# bldc_driver_board_easyeda.net
KiCad netlist of a schematic drawn in EasyEDA Pro
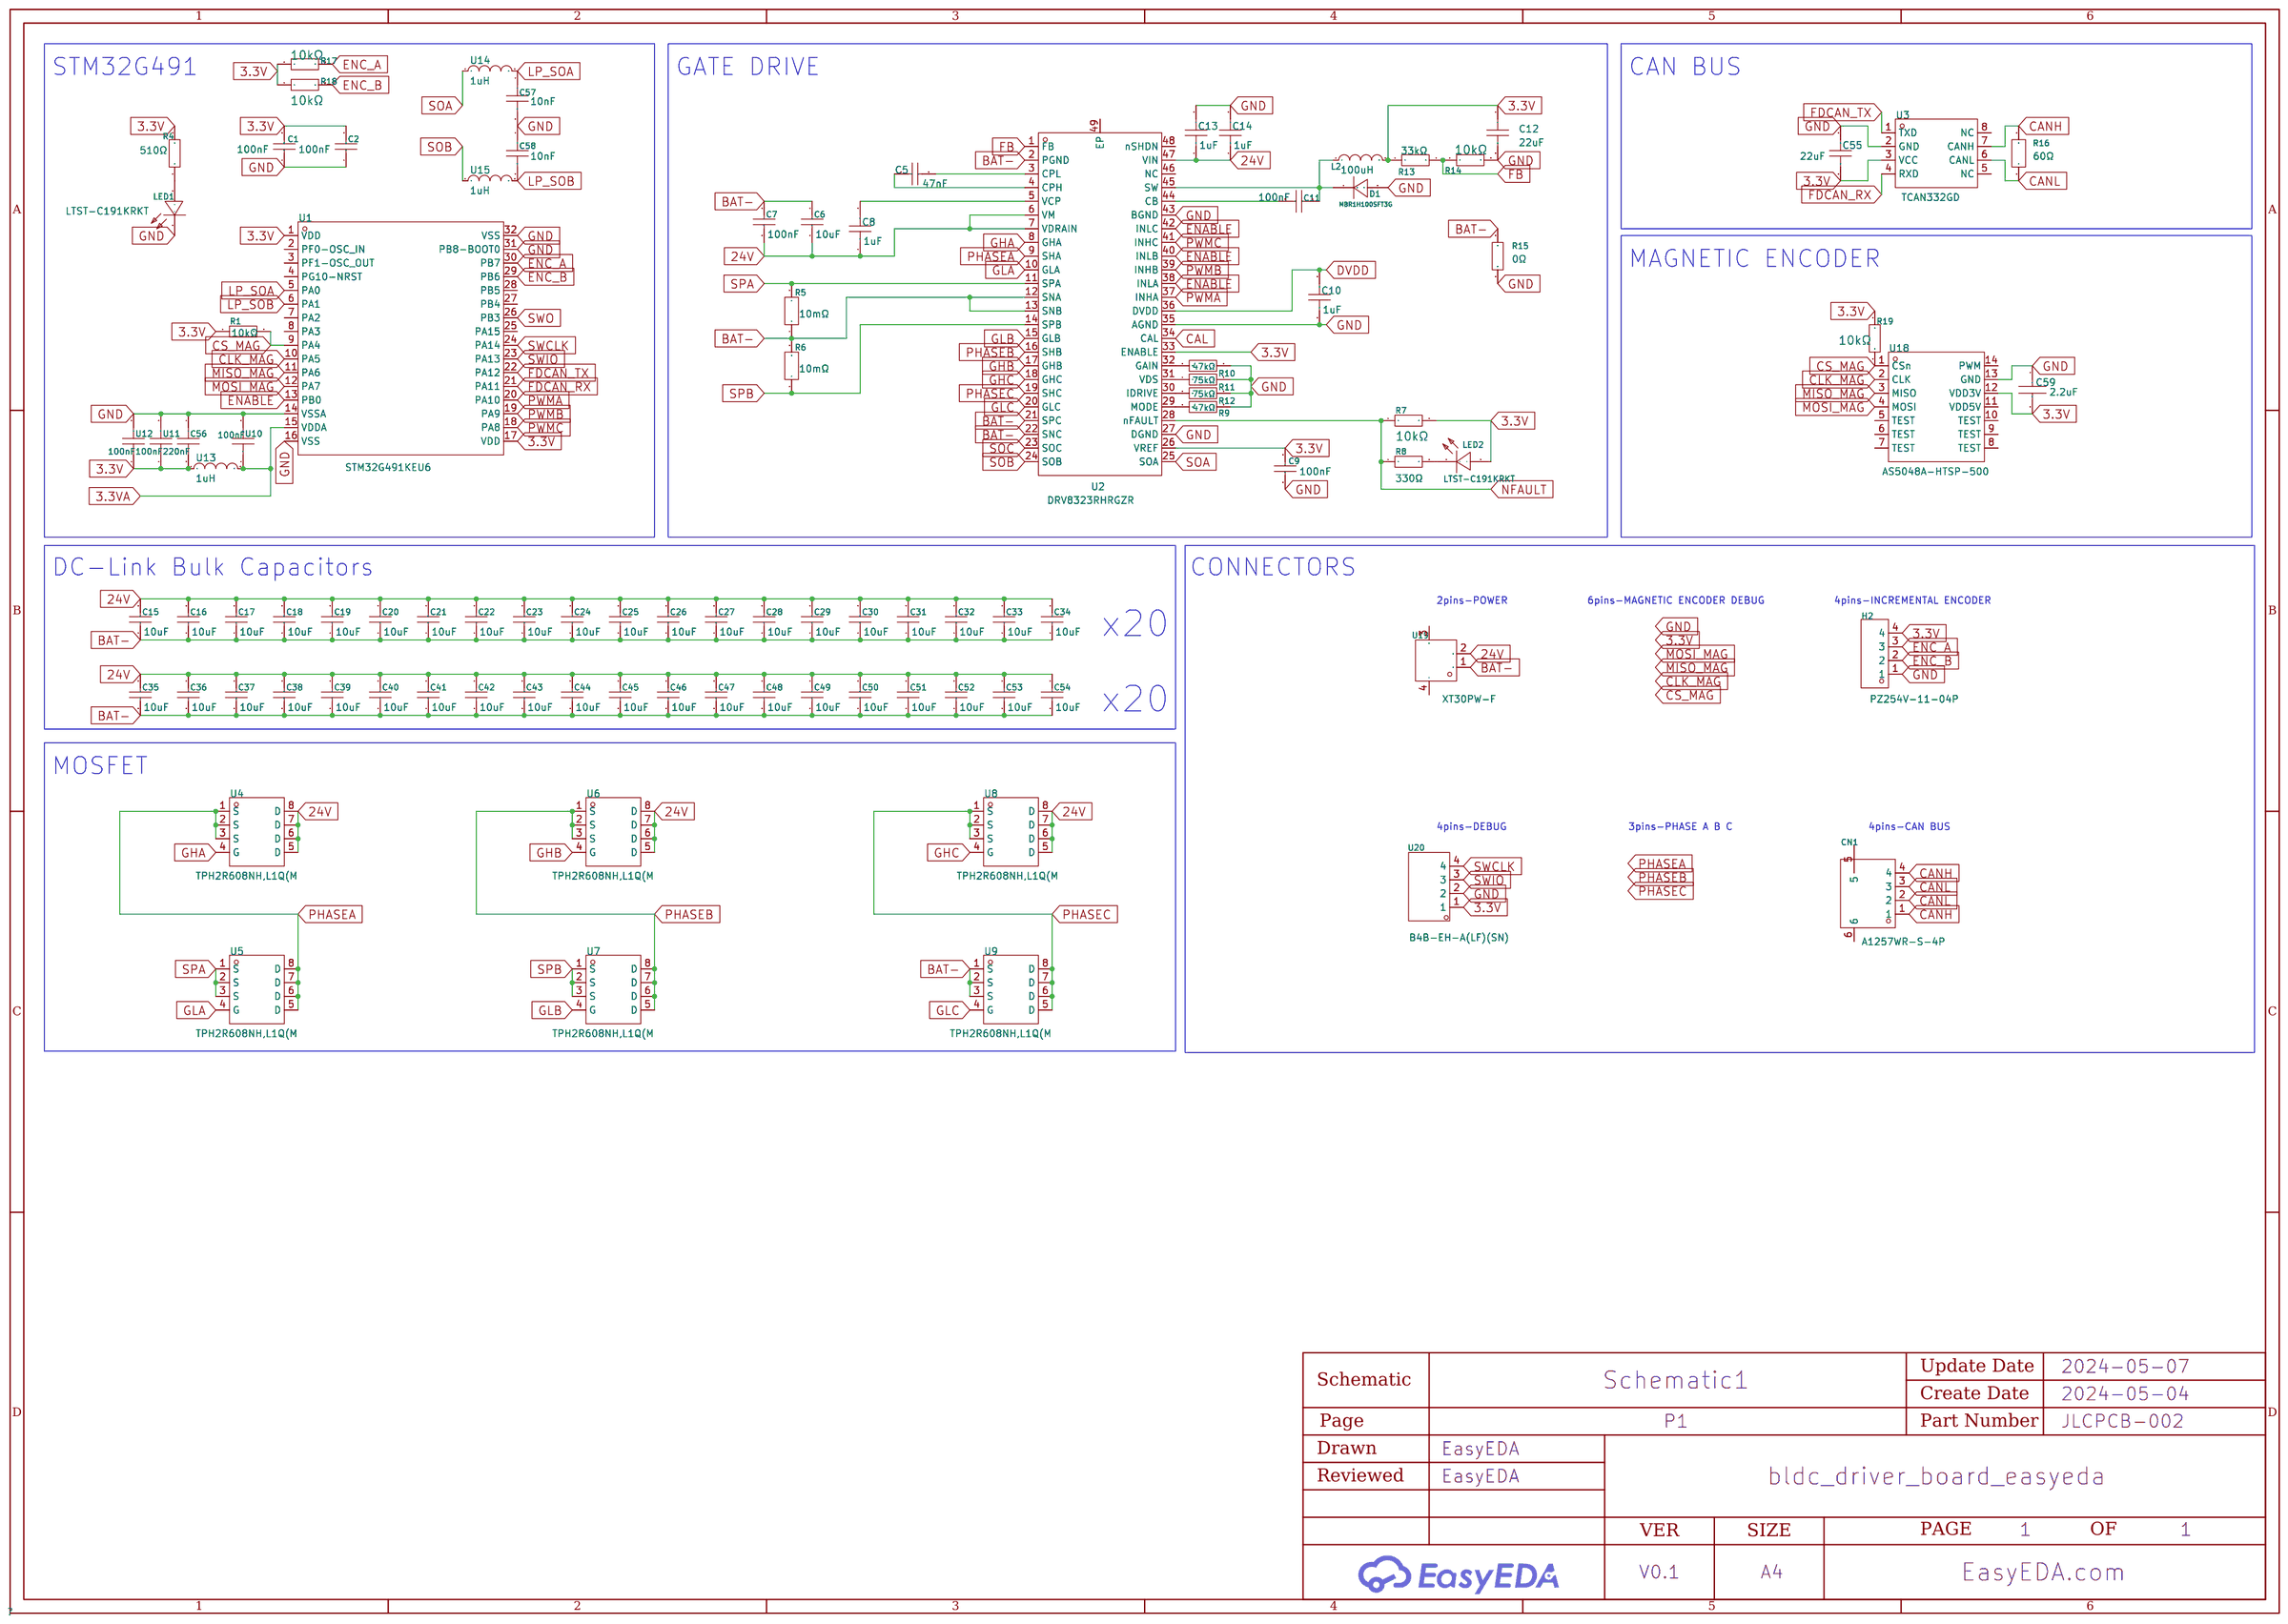
[diagram p0: schematic sheet]

(export (version "E")
  (design (tool "Eeschema 10.0.6"))
  (components
    (comp (ref "C1")
      (value "100nF")
      (footprint "easyedapro:C0603")
      (fields
        (field (name "Manufacturer Part") "CL10B104KO8NNNC")
        (field (name "Manufacturer") "SAMSUNG(三星)")
      )
      (libsource (lib "easyedapro") (part "CL10B104KO8NNNC"))
    )
    (comp (ref "C2")
      (value "100nF")
      (footprint "easyedapro:C0603")
      (fields
        (field (name "Manufacturer Part") "CL10B104KO8NNNC")
        (field (name "Manufacturer") "SAMSUNG(三星)")
      )
      (libsource (lib "easyedapro") (part "CL10B104KO8NNNC"))
    )
    (comp (ref "C5")
      (value "47nF")
      (footprint "easyedapro:C0805")
      (fields (field (name "Manufacturer Part") "0805B473K500NT") (field (name "Manufacturer") "FH(风华)"))
      (libsource (lib "easyedapro") (part "0805B473K500NT"))
    )
    (comp (ref "C6")
      (value "10uF")
      (footprint "easyedapro:C1206")
      (fields
        (field (name "Manufacturer Part") "CL31A106KBHNNNE")
        (field (name "Manufacturer") "SAMSUNG(三星)")
      )
      (libsource (lib "easyedapro") (part "CL31A106KBHNNNE"))
    )
    (comp (ref "C7")
      (value "100nF")
      (footprint "easyedapro:C1206")
      (fields (field (name "Manufacturer Part") "1206B104K500NT") (field (name "Manufacturer") "FH(风华)"))
      (libsource (lib "easyedapro") (part "1206B104K500NT"))
    )
    (comp (ref "C8")
      (value "1uF")
      (footprint "easyedapro:C0603")
      (fields
        (field (name "Manufacturer Part") "CL10A105KB8NNNC")
        (field (name "Manufacturer") "SAMSUNG(三星)")
      )
      (libsource (lib "easyedapro") (part "CL10A105KB8NNNC"))
    )
    (comp (ref "C9")
      (value "100nF")
      (footprint "easyedapro:C0603")
      (fields
        (field (name "Manufacturer Part") "CL10B104KO8NNNC")
        (field (name "Manufacturer") "SAMSUNG(三星)")
      )
      (libsource (lib "easyedapro") (part "CL10B104KO8NNNC"))
    )
    (comp (ref "C10")
      (value "1uF")
      (footprint "easyedapro:C0603")
      (fields
        (field (name "Manufacturer Part") "CL10A105KB8NNNC")
        (field (name "Manufacturer") "SAMSUNG(三星)")
      )
      (libsource (lib "easyedapro") (part "CL10A105KB8NNNC"))
    )
    (comp (ref "C11")
      (value "100nF")
      (footprint "easyedapro:C1206")
      (fields (field (name "Manufacturer Part") "1206B104K500NT") (field (name "Manufacturer") "FH(风华)"))
      (libsource (lib "easyedapro") (part "1206B104K500NT"))
    )
    (comp (ref "C12")
      (value "22uF")
      (footprint "easyedapro:C0603")
      (fields
        (field (name "Manufacturer Part") "CL10A226MQ8NRNE")
        (field (name "Manufacturer") "SAMSUNG(三星)")
      )
      (libsource (lib "easyedapro") (part "CL10A226MQ8NRNE"))
    )
    (comp (ref "C13")
      (value "1uF")
      (footprint "easyedapro:C0603")
      (fields
        (field (name "Manufacturer Part") "CL10A105KB8NNNC")
        (field (name "Manufacturer") "SAMSUNG(三星)")
      )
      (libsource (lib "easyedapro") (part "CL10A105KB8NNNC"))
    )
    (comp (ref "C14")
      (value "1uF")
      (footprint "easyedapro:C0603")
      (fields
        (field (name "Manufacturer Part") "CL10A105KB8NNNC")
        (field (name "Manufacturer") "SAMSUNG(三星)")
      )
      (libsource (lib "easyedapro") (part "CL10A105KB8NNNC"))
    )
    (comp (ref "C15")
      (value "10uF")
      (footprint "easyedapro:C1206")
      (fields
        (field (name "Manufacturer Part") "CL31A106KBHNNNE")
        (field (name "Manufacturer") "SAMSUNG(三星)")
      )
      (libsource (lib "easyedapro") (part "CL31A106KBHNNNE"))
    )
    (comp (ref "C16")
      (value "10uF")
      (footprint "easyedapro:C1206")
      (fields
        (field (name "Manufacturer Part") "CL31A106KBHNNNE")
        (field (name "Manufacturer") "SAMSUNG(三星)")
      )
      (libsource (lib "easyedapro") (part "CL31A106KBHNNNE"))
    )
    (comp (ref "C17")
      (value "10uF")
      (footprint "easyedapro:C1206")
      (fields
        (field (name "Manufacturer Part") "CL31A106KBHNNNE")
        (field (name "Manufacturer") "SAMSUNG(三星)")
      )
      (libsource (lib "easyedapro") (part "CL31A106KBHNNNE"))
    )
    (comp (ref "C18")
      (value "10uF")
      (footprint "easyedapro:C1206")
      (fields
        (field (name "Manufacturer Part") "CL31A106KBHNNNE")
        (field (name "Manufacturer") "SAMSUNG(三星)")
      )
      (libsource (lib "easyedapro") (part "CL31A106KBHNNNE"))
    )
    (comp (ref "C19")
      (value "10uF")
      (footprint "easyedapro:C1206")
      (fields
        (field (name "Manufacturer Part") "CL31A106KBHNNNE")
        (field (name "Manufacturer") "SAMSUNG(三星)")
      )
      (libsource (lib "easyedapro") (part "CL31A106KBHNNNE"))
    )
    (comp (ref "C20")
      (value "10uF")
      (footprint "easyedapro:C1206")
      (fields
        (field (name "Manufacturer Part") "CL31A106KBHNNNE")
        (field (name "Manufacturer") "SAMSUNG(三星)")
      )
      (libsource (lib "easyedapro") (part "CL31A106KBHNNNE"))
    )
    (comp (ref "C21")
      (value "10uF")
      (footprint "easyedapro:C1206")
      (fields
        (field (name "Manufacturer Part") "CL31A106KBHNNNE")
        (field (name "Manufacturer") "SAMSUNG(三星)")
      )
      (libsource (lib "easyedapro") (part "CL31A106KBHNNNE"))
    )
    (comp (ref "C22")
      (value "10uF")
      (footprint "easyedapro:C1206")
      (fields
        (field (name "Manufacturer Part") "CL31A106KBHNNNE")
        (field (name "Manufacturer") "SAMSUNG(三星)")
      )
      (libsource (lib "easyedapro") (part "CL31A106KBHNNNE"))
    )
    (comp (ref "C23")
      (value "10uF")
      (footprint "easyedapro:C1206")
      (fields
        (field (name "Manufacturer Part") "CL31A106KBHNNNE")
        (field (name "Manufacturer") "SAMSUNG(三星)")
      )
      (libsource (lib "easyedapro") (part "CL31A106KBHNNNE"))
    )
    (comp (ref "C24")
      (value "10uF")
      (footprint "easyedapro:C1206")
      (fields
        (field (name "Manufacturer Part") "CL31A106KBHNNNE")
        (field (name "Manufacturer") "SAMSUNG(三星)")
      )
      (libsource (lib "easyedapro") (part "CL31A106KBHNNNE"))
    )
    (comp (ref "C25")
      (value "10uF")
      (footprint "easyedapro:C1206")
      (fields
        (field (name "Manufacturer Part") "CL31A106KBHNNNE")
        (field (name "Manufacturer") "SAMSUNG(三星)")
      )
      (libsource (lib "easyedapro") (part "CL31A106KBHNNNE"))
    )
    (comp (ref "C26")
      (value "10uF")
      (footprint "easyedapro:C1206")
      (fields
        (field (name "Manufacturer Part") "CL31A106KBHNNNE")
        (field (name "Manufacturer") "SAMSUNG(三星)")
      )
      (libsource (lib "easyedapro") (part "CL31A106KBHNNNE"))
    )
    (comp (ref "C27")
      (value "10uF")
      (footprint "easyedapro:C1206")
      (fields
        (field (name "Manufacturer Part") "CL31A106KBHNNNE")
        (field (name "Manufacturer") "SAMSUNG(三星)")
      )
      (libsource (lib "easyedapro") (part "CL31A106KBHNNNE"))
    )
    (comp (ref "C28")
      (value "10uF")
      (footprint "easyedapro:C1206")
      (fields
        (field (name "Manufacturer Part") "CL31A106KBHNNNE")
        (field (name "Manufacturer") "SAMSUNG(三星)")
      )
      (libsource (lib "easyedapro") (part "CL31A106KBHNNNE"))
    )
    (comp (ref "C29")
      (value "10uF")
      (footprint "easyedapro:C1206")
      (fields
        (field (name "Manufacturer Part") "CL31A106KBHNNNE")
        (field (name "Manufacturer") "SAMSUNG(三星)")
      )
      (libsource (lib "easyedapro") (part "CL31A106KBHNNNE"))
    )
    (comp (ref "C30")
      (value "10uF")
      (footprint "easyedapro:C1206")
      (fields
        (field (name "Manufacturer Part") "CL31A106KBHNNNE")
        (field (name "Manufacturer") "SAMSUNG(三星)")
      )
      (libsource (lib "easyedapro") (part "CL31A106KBHNNNE"))
    )
    (comp (ref "C31")
      (value "10uF")
      (footprint "easyedapro:C1206")
      (fields
        (field (name "Manufacturer Part") "CL31A106KBHNNNE")
        (field (name "Manufacturer") "SAMSUNG(三星)")
      )
      (libsource (lib "easyedapro") (part "CL31A106KBHNNNE"))
    )
    (comp (ref "C32")
      (value "10uF")
      (footprint "easyedapro:C1206")
      (fields
        (field (name "Manufacturer Part") "CL31A106KBHNNNE")
        (field (name "Manufacturer") "SAMSUNG(三星)")
      )
      (libsource (lib "easyedapro") (part "CL31A106KBHNNNE"))
    )
    (comp (ref "C33")
      (value "10uF")
      (footprint "easyedapro:C1206")
      (fields
        (field (name "Manufacturer Part") "CL31A106KBHNNNE")
        (field (name "Manufacturer") "SAMSUNG(三星)")
      )
      (libsource (lib "easyedapro") (part "CL31A106KBHNNNE"))
    )
    (comp (ref "C34")
      (value "10uF")
      (footprint "easyedapro:C1206")
      (fields
        (field (name "Manufacturer Part") "CL31A106KBHNNNE")
        (field (name "Manufacturer") "SAMSUNG(三星)")
      )
      (libsource (lib "easyedapro") (part "CL31A106KBHNNNE"))
    )
    (comp (ref "C35")
      (value "10uF")
      (footprint "easyedapro:C1206")
      (fields
        (field (name "Manufacturer Part") "CL31A106KBHNNNE")
        (field (name "Manufacturer") "SAMSUNG(三星)")
      )
      (libsource (lib "easyedapro") (part "CL31A106KBHNNNE"))
    )
    (comp (ref "C36")
      (value "10uF")
      (footprint "easyedapro:C1206")
      (fields
        (field (name "Manufacturer Part") "CL31A106KBHNNNE")
        (field (name "Manufacturer") "SAMSUNG(三星)")
      )
      (libsource (lib "easyedapro") (part "CL31A106KBHNNNE"))
    )
    (comp (ref "C37")
      (value "10uF")
      (footprint "easyedapro:C1206")
      (fields
        (field (name "Manufacturer Part") "CL31A106KBHNNNE")
        (field (name "Manufacturer") "SAMSUNG(三星)")
      )
      (libsource (lib "easyedapro") (part "CL31A106KBHNNNE"))
    )
    (comp (ref "C38")
      (value "10uF")
      (footprint "easyedapro:C1206")
      (fields
        (field (name "Manufacturer Part") "CL31A106KBHNNNE")
        (field (name "Manufacturer") "SAMSUNG(三星)")
      )
      (libsource (lib "easyedapro") (part "CL31A106KBHNNNE"))
    )
    (comp (ref "C39")
      (value "10uF")
      (footprint "easyedapro:C1206")
      (fields
        (field (name "Manufacturer Part") "CL31A106KBHNNNE")
        (field (name "Manufacturer") "SAMSUNG(三星)")
      )
      (libsource (lib "easyedapro") (part "CL31A106KBHNNNE"))
    )
    (comp (ref "C40")
      (value "10uF")
      (footprint "easyedapro:C1206")
      (fields
        (field (name "Manufacturer Part") "CL31A106KBHNNNE")
        (field (name "Manufacturer") "SAMSUNG(三星)")
      )
      (libsource (lib "easyedapro") (part "CL31A106KBHNNNE"))
    )
    (comp (ref "C41")
      (value "10uF")
      (footprint "easyedapro:C1206")
      (fields
        (field (name "Manufacturer Part") "CL31A106KBHNNNE")
        (field (name "Manufacturer") "SAMSUNG(三星)")
      )
      (libsource (lib "easyedapro") (part "CL31A106KBHNNNE"))
    )
    (comp (ref "C42")
      (value "10uF")
      (footprint "easyedapro:C1206")
      (fields
        (field (name "Manufacturer Part") "CL31A106KBHNNNE")
        (field (name "Manufacturer") "SAMSUNG(三星)")
      )
      (libsource (lib "easyedapro") (part "CL31A106KBHNNNE"))
    )
    (comp (ref "C43")
      (value "10uF")
      (footprint "easyedapro:C1206")
      (fields
        (field (name "Manufacturer Part") "CL31A106KBHNNNE")
        (field (name "Manufacturer") "SAMSUNG(三星)")
      )
      (libsource (lib "easyedapro") (part "CL31A106KBHNNNE"))
    )
    (comp (ref "C44")
      (value "10uF")
      (footprint "easyedapro:C1206")
      (fields
        (field (name "Manufacturer Part") "CL31A106KBHNNNE")
        (field (name "Manufacturer") "SAMSUNG(三星)")
      )
      (libsource (lib "easyedapro") (part "CL31A106KBHNNNE"))
    )
    (comp (ref "C45")
      (value "10uF")
      (footprint "easyedapro:C1206")
      (fields
        (field (name "Manufacturer Part") "CL31A106KBHNNNE")
        (field (name "Manufacturer") "SAMSUNG(三星)")
      )
      (libsource (lib "easyedapro") (part "CL31A106KBHNNNE"))
    )
    (comp (ref "C46")
      (value "10uF")
      (footprint "easyedapro:C1206")
      (fields
        (field (name "Manufacturer Part") "CL31A106KBHNNNE")
        (field (name "Manufacturer") "SAMSUNG(三星)")
      )
      (libsource (lib "easyedapro") (part "CL31A106KBHNNNE"))
    )
    (comp (ref "C47")
      (value "10uF")
      (footprint "easyedapro:C1206")
      (fields
        (field (name "Manufacturer Part") "CL31A106KBHNNNE")
        (field (name "Manufacturer") "SAMSUNG(三星)")
      )
      (libsource (lib "easyedapro") (part "CL31A106KBHNNNE"))
    )
    (comp (ref "C48")
      (value "10uF")
      (footprint "easyedapro:C1206")
      (fields
        (field (name "Manufacturer Part") "CL31A106KBHNNNE")
        (field (name "Manufacturer") "SAMSUNG(三星)")
      )
      (libsource (lib "easyedapro") (part "CL31A106KBHNNNE"))
    )
    (comp (ref "C49")
      (value "10uF")
      (footprint "easyedapro:C1206")
      (fields
        (field (name "Manufacturer Part") "CL31A106KBHNNNE")
        (field (name "Manufacturer") "SAMSUNG(三星)")
      )
      (libsource (lib "easyedapro") (part "CL31A106KBHNNNE"))
    )
    (comp (ref "C50")
      (value "10uF")
      (footprint "easyedapro:C1206")
      (fields
        (field (name "Manufacturer Part") "CL31A106KBHNNNE")
        (field (name "Manufacturer") "SAMSUNG(三星)")
      )
      (libsource (lib "easyedapro") (part "CL31A106KBHNNNE"))
    )
    (comp (ref "C51")
      (value "10uF")
      (footprint "easyedapro:C1206")
      (fields
        (field (name "Manufacturer Part") "CL31A106KBHNNNE")
        (field (name "Manufacturer") "SAMSUNG(三星)")
      )
      (libsource (lib "easyedapro") (part "CL31A106KBHNNNE"))
    )
    (comp (ref "C52")
      (value "10uF")
      (footprint "easyedapro:C1206")
      (fields
        (field (name "Manufacturer Part") "CL31A106KBHNNNE")
        (field (name "Manufacturer") "SAMSUNG(三星)")
      )
      (libsource (lib "easyedapro") (part "CL31A106KBHNNNE"))
    )
    (comp (ref "C53")
      (value "10uF")
      (footprint "easyedapro:C1206")
      (fields
        (field (name "Manufacturer Part") "CL31A106KBHNNNE")
        (field (name "Manufacturer") "SAMSUNG(三星)")
      )
      (libsource (lib "easyedapro") (part "CL31A106KBHNNNE"))
    )
    (comp (ref "C54")
      (value "10uF")
      (footprint "easyedapro:C1206")
      (fields
        (field (name "Manufacturer Part") "CL31A106KBHNNNE")
        (field (name "Manufacturer") "SAMSUNG(三星)")
      )
      (libsource (lib "easyedapro") (part "CL31A106KBHNNNE"))
    )
    (comp (ref "C55")
      (value "22uF")
      (footprint "easyedapro:C0603")
      (fields
        (field (name "Manufacturer Part") "CL10A226MQ8NRNE")
        (field (name "Manufacturer") "SAMSUNG(三星)")
      )
      (libsource (lib "easyedapro") (part "CL10A226MQ8NRNE"))
    )
    (comp (ref "C56")
      (value "220nF")
      (footprint "easyedapro:C0201")
      (fields (field (name "Manufacturer Part") "C0603X5R0J224KT00NN") (field (name "Manufacturer") "TDK"))
      (libsource (lib "easyedapro") (part "C0603X5R0J224KT00NN"))
    )
    (comp (ref "C57")
      (value "10nF")
      (footprint "easyedapro:C01005")
      (fields
        (field (name "Manufacturer Part") "CC0100KRX5R5BB103")
        (field (name "Manufacturer") "YAGEO(国巨)")
      )
      (libsource (lib "easyedapro") (part "CC0100KRX5R5BB103"))
    )
    (comp (ref "C58")
      (value "10nF")
      (footprint "easyedapro:C01005")
      (fields
        (field (name "Manufacturer Part") "CC0100KRX5R5BB103")
        (field (name "Manufacturer") "YAGEO(国巨)")
      )
      (libsource (lib "easyedapro") (part "CC0100KRX5R5BB103"))
    )
    (comp (ref "C59")
      (value "2.2uF")
      (footprint "easyedapro:C0402")
      (fields
        (field (name "Manufacturer Part") "CL05A225MQ5NSNC")
        (field (name "Manufacturer") "SAMSUNG(三星)")
      )
      (libsource (lib "easyedapro") (part "CL05A225MQ5NSNC"))
    )
    (comp (ref "CN1")
      (value "A1257WR-S-4P")
      (footprint "easyedapro:CONN-SMD_A1257WR-S-4P")
      (fields (field (name "Manufacturer") "CJT(长江连接器)"))
      (libsource (lib "easyedapro") (part "A1257WR-S-4P"))
    )
    (comp (ref "D1")
      (value "MBR1H100SFT3G")
      (footprint "easyedapro:SOD-123F_L2.8-W1.8-LS3.7-RD")
      (fields (field (name "Manufacturer") "onsemi(安森美)"))
      (libsource (lib "easyedapro") (part "MBR1H100SFT3G"))
    )
    (comp (ref "H2")
      (value "PZ254V-11-04P")
      (footprint "easyedapro:HDR-TH_4P-P2.54-V-M")
      (fields (field (name "Manufacturer") "XFCN(兴飞)"))
      (libsource (lib "easyedapro") (part "PZ254V-11-04P"))
    )
    (comp (ref "L2")
      (value "100uH")
      (footprint "easyedapro:IND-SMD_L4.0-W4.0")
      (fields
        (field (name "Manufacturer Part") "ASPIAIG-S4035-101M-T")
        (field (name "Manufacturer") "ABRACON")
      )
      (libsource (lib "easyedapro") (part "ASPIAIG-S4035-101M-T"))
    )
    (comp (ref "LED1")
      (value "LTST-C191KRKT")
      (footprint "easyedapro:LED0603-RD")
      (fields (field (name "Manufacturer") "LITEON(光宝)"))
      (libsource (lib "easyedapro") (part "LTST-C191KRKT"))
    )
    (comp (ref "LED2")
      (value "LTST-C191KRKT")
      (footprint "easyedapro:LED0603-RD")
      (fields (field (name "Manufacturer") "LITEON(光宝)"))
      (libsource (lib "easyedapro") (part "LTST-C191KRKT"))
    )
    (comp (ref "R1")
      (value "10kΩ")
      (footprint "easyedapro:R0603")
      (fields
        (field (name "Manufacturer Part") "0603WAF1002T5E")
        (field (name "Manufacturer") "UNI-ROYAL(厚声)")
      )
      (libsource (lib "easyedapro") (part "0603WAF1002T5E"))
    )
    (comp (ref "R4")
      (value "510Ω")
      (footprint "easyedapro:R0603")
      (fields
        (field (name "Manufacturer Part") "0603WAF5100T5E")
        (field (name "Manufacturer") "UNI-ROYAL(厚声)")
      )
      (libsource (lib "easyedapro") (part "0603WAF5100T5E"))
    )
    (comp (ref "R5")
      (value "10mΩ")
      (footprint "easyedapro:RES-SMD_L6.4-W3.2-R2512")
      (fields
        (field (name "Manufacturer Part") "HoJLR2512-3W-10mR-1%")
        (field (name "Manufacturer") "Milliohm(毫欧)")
      )
      (libsource (lib "easyedapro") (part "HOJLR2512-3W-10MR-1%"))
    )
    (comp (ref "R6")
      (value "10mΩ")
      (footprint "easyedapro:RES-SMD_L6.4-W3.2-R2512")
      (fields
        (field (name "Manufacturer Part") "HoJLR2512-3W-10mR-1%")
        (field (name "Manufacturer") "Milliohm(毫欧)")
      )
      (libsource (lib "easyedapro") (part "HOJLR2512-3W-10MR-1%"))
    )
    (comp (ref "R7")
      (value "10kΩ")
      (footprint "easyedapro:R0603")
      (fields
        (field (name "Manufacturer Part") "0603WAF1002T5E")
        (field (name "Manufacturer") "UNI-ROYAL(厚声)")
      )
      (libsource (lib "easyedapro") (part "0603WAF1002T5E"))
    )
    (comp (ref "R8")
      (value "330Ω")
      (footprint "easyedapro:R0603")
      (fields
        (field (name "Manufacturer Part") "0603WAF3300T5E")
        (field (name "Manufacturer") "UNI-ROYAL(厚声)")
      )
      (libsource (lib "easyedapro") (part "0603WAF3300T5E"))
    )
    (comp (ref "R9")
      (value "47kΩ")
      (footprint "easyedapro:R0603")
      (fields
        (field (name "Manufacturer Part") "0603WAF4702T5E")
        (field (name "Manufacturer") "UNI-ROYAL(厚声)")
      )
      (libsource (lib "easyedapro") (part "0603WAF4702T5E"))
    )
    (comp (ref "R10")
      (value "47kΩ")
      (footprint "easyedapro:R0603")
      (fields
        (field (name "Manufacturer Part") "0603WAF4702T5E")
        (field (name "Manufacturer") "UNI-ROYAL(厚声)")
      )
      (libsource (lib "easyedapro") (part "0603WAF4702T5E"))
    )
    (comp (ref "R11")
      (value "75kΩ")
      (footprint "easyedapro:R0603")
      (fields
        (field (name "Manufacturer Part") "0603WAF7502T5E")
        (field (name "Manufacturer") "UNI-ROYAL(厚声)")
      )
      (libsource (lib "easyedapro") (part "0603WAF7502T5E"))
    )
    (comp (ref "R12")
      (value "75kΩ")
      (footprint "easyedapro:R0603")
      (fields
        (field (name "Manufacturer Part") "0603WAF7502T5E")
        (field (name "Manufacturer") "UNI-ROYAL(厚声)")
      )
      (libsource (lib "easyedapro") (part "0603WAF7502T5E"))
    )
    (comp (ref "R13")
      (value "33kΩ")
      (footprint "easyedapro:R0603")
      (fields
        (field (name "Manufacturer Part") "0603WAF3302T5E")
        (field (name "Manufacturer") "UNI-ROYAL(厚声)")
      )
      (libsource (lib "easyedapro") (part "0603WAF3302T5E"))
    )
    (comp (ref "R14")
      (value "10kΩ")
      (footprint "easyedapro:R0603")
      (fields
        (field (name "Manufacturer Part") "0603WAF1002T5E")
        (field (name "Manufacturer") "UNI-ROYAL(厚声)")
      )
      (libsource (lib "easyedapro") (part "0603WAF1002T5E"))
    )
    (comp (ref "R15")
      (value "0Ω")
      (footprint "easyedapro:R1206")
      (fields
        (field (name "Manufacturer Part") "1206W4F0000T5E")
        (field (name "Manufacturer") "UNI-ROYAL(厚声)")
      )
      (libsource (lib "easyedapro") (part "1206W4F0000T5E"))
    )
    (comp (ref "R16")
      (value "60Ω")
      (footprint "easyedapro:R0603")
      (fields (field (name "Manufacturer Part") "RTT0360R0FTP") (field (name "Manufacturer") "RALEC(旺诠)"))
      (libsource (lib "easyedapro") (part "RTT0360R0FTP"))
    )
    (comp (ref "R17")
      (value "10kΩ")
      (footprint "easyedapro:R0603")
      (fields
        (field (name "Manufacturer Part") "0603WAF1002T5E")
        (field (name "Manufacturer") "UNI-ROYAL(厚声)")
      )
      (libsource (lib "easyedapro") (part "0603WAF1002T5E"))
    )
    (comp (ref "R18")
      (value "10kΩ")
      (footprint "easyedapro:R0603")
      (fields
        (field (name "Manufacturer Part") "0603WAF1002T5E")
        (field (name "Manufacturer") "UNI-ROYAL(厚声)")
      )
      (libsource (lib "easyedapro") (part "0603WAF1002T5E"))
    )
    (comp (ref "R19")
      (value "10kΩ")
      (footprint "easyedapro:R0603")
      (fields
        (field (name "Manufacturer Part") "0603WAF1002T5E")
        (field (name "Manufacturer") "UNI-ROYAL(厚声)")
      )
      (libsource (lib "easyedapro") (part "0603WAF1002T5E"))
    )
    (comp (ref "U1")
      (value "STM32G491KEU6")
      (footprint "easyedapro:UFQFPN-32_L5.0-W5.0-P0.50-TL-1")
      (fields (field (name "Manufacturer") "ST(意法半导体)"))
      (libsource (lib "easyedapro") (part "STM32G491KEU6"))
    )
    (comp (ref "U2")
      (value "DRV8323RHRGZR")
      (footprint "easyedapro:VQFN-48_L7.0-W7.0-P0.50-TL-EP5.1")
      (fields (field (name "Manufacturer") "TI(德州仪器)"))
      (libsource (lib "easyedapro") (part "DRV8323RHRGZR"))
    )
    (comp (ref "U3")
      (value "TCAN332GD")
      (footprint "easyedapro:SOIC-8_L4.9-W3.9-P1.27-LS6.0-BL")
      (fields (field (name "Manufacturer") "TI(德州仪器)"))
      (libsource (lib "easyedapro") (part "TCAN332GD"))
    )
    (comp (ref "U4")
      (value "TPH2R608NH,L1Q(M")
      (footprint "easyedapro:POWERVDFN-8_L5.0-W5.0-P1.27-LS6.0-BL")
      (fields (field (name "Manufacturer") "TOSHIBA(东芝)"))
      (libsource (lib "easyedapro") (part "TPH2R608NH,L1Q(M"))
    )
    (comp (ref "U5")
      (value "TPH2R608NH,L1Q(M")
      (footprint "easyedapro:POWERVDFN-8_L5.0-W5.0-P1.27-LS6.0-BL")
      (fields (field (name "Manufacturer") "TOSHIBA(东芝)"))
      (libsource (lib "easyedapro") (part "TPH2R608NH,L1Q(M"))
    )
    (comp (ref "U6")
      (value "TPH2R608NH,L1Q(M")
      (footprint "easyedapro:POWERVDFN-8_L5.0-W5.0-P1.27-LS6.0-BL")
      (fields (field (name "Manufacturer") "TOSHIBA(东芝)"))
      (libsource (lib "easyedapro") (part "TPH2R608NH,L1Q(M"))
    )
    (comp (ref "U7")
      (value "TPH2R608NH,L1Q(M")
      (footprint "easyedapro:POWERVDFN-8_L5.0-W5.0-P1.27-LS6.0-BL")
      (fields (field (name "Manufacturer") "TOSHIBA(东芝)"))
      (libsource (lib "easyedapro") (part "TPH2R608NH,L1Q(M"))
    )
    (comp (ref "U8")
      (value "TPH2R608NH,L1Q(M")
      (footprint "easyedapro:POWERVDFN-8_L5.0-W5.0-P1.27-LS6.0-BL")
      (fields (field (name "Manufacturer") "TOSHIBA(东芝)"))
      (libsource (lib "easyedapro") (part "TPH2R608NH,L1Q(M"))
    )
    (comp (ref "U9")
      (value "TPH2R608NH,L1Q(M")
      (footprint "easyedapro:POWERVDFN-8_L5.0-W5.0-P1.27-LS6.0-BL")
      (fields (field (name "Manufacturer") "TOSHIBA(东芝)"))
      (libsource (lib "easyedapro") (part "TPH2R608NH,L1Q(M"))
    )
    (comp (ref "U10")
      (value "100nF")
      (footprint "easyedapro:C0603")
      (fields (field (name "Manufacturer Part") "06036D104KAT2A") (field (name "Manufacturer") "Kyocera AVX"))
      (libsource (lib "easyedapro") (part "06036D104KAT2A"))
    )
    (comp (ref "U11")
      (value "100nF")
      (footprint "easyedapro:C0603")
      (fields (field (name "Manufacturer Part") "06036D104KAT2A") (field (name "Manufacturer") "Kyocera AVX"))
      (libsource (lib "easyedapro") (part "06036D104KAT2A"))
    )
    (comp (ref "U12")
      (value "100nF")
      (footprint "easyedapro:C0603")
      (fields (field (name "Manufacturer Part") "06036D104KAT2A") (field (name "Manufacturer") "Kyocera AVX"))
      (libsource (lib "easyedapro") (part "06036D104KAT2A"))
    )
    (comp (ref "U13")
      (value "1uH")
      (footprint "easyedapro:L0603")
      (fields (field (name "Manufacturer Part") "YL160808-1R0K") (field (name "Manufacturer") "YJYCOIN(益嘉源)"))
      (libsource (lib "easyedapro") (part "YL160808-1R0K"))
    )
    (comp (ref "U14")
      (value "1uH")
      (footprint "easyedapro:L0603")
      (fields (field (name "Manufacturer Part") "YL160808-1R0K") (field (name "Manufacturer") "YJYCOIN(益嘉源)"))
      (libsource (lib "easyedapro") (part "YL160808-1R0K"))
    )
    (comp (ref "U15")
      (value "1uH")
      (footprint "easyedapro:L0603")
      (fields (field (name "Manufacturer Part") "YL160808-1R0K") (field (name "Manufacturer") "YJYCOIN(益嘉源)"))
      (libsource (lib "easyedapro") (part "YL160808-1R0K"))
    )
    (comp (ref "U18")
      (value "AS5048A-HTSP-500")
      (footprint "easyedapro:TSSOP-14_L5.0-W4.4-P0.65-LS6.4-BL")
      (fields (field (name "Manufacturer") "ams(艾迈斯半导体)"))
      (libsource (lib "easyedapro") (part "AS5048A-HTSP-500"))
    )
    (comp (ref "U19")
      (value "XT30PW-F")
      (footprint "easyedapro:CONN-TH_XT30PW-F-1")
      (fields (field (name "Manufacturer") "AMASS(艾迈斯)"))
      (libsource (lib "easyedapro") (part "XT30PW-F"))
    )
    (comp (ref "U20")
      (value "B4B-EH-A(LF)(SN)")
      (footprint "easyedapro:CONN-TH_B4B-EH-A-LF-SN")
      (fields (field (name "Manufacturer") "JST"))
      (libsource (lib "easyedapro") (part "B4B-EH-A(LF)(SN)"))
    )
  )
  (nets
    (net (code "1") (name "3.3V") (class "Default")
      (node (ref "C1") (pin "2") (pinfunction "2_2") (pintype "input"))
      (node (ref "C12") (pin "1") (pinfunction "1_1") (pintype "unspecified"))
      (node (ref "C2") (pin "2") (pinfunction "2_2") (pintype "input"))
      (node (ref "C55") (pin "2") (pinfunction "2_2") (pintype "unspecified"))
      (node (ref "C56") (pin "2") (pinfunction "2_2") (pintype "input"))
      (node (ref "C59") (pin "2") (pinfunction "2_2") (pintype "unspecified"))
      (node (ref "C9") (pin "2") (pinfunction "2_2") (pintype "input"))
      (node (ref "H2") (pin "4") (pinfunction "4_4") (pintype "unspecified"))
      (node (ref "L2") (pin "2") (pinfunction "2_2") (pintype "input"))
      (node (ref "LED2") (pin "2") (pinfunction "+_2") (pintype "input"))
      (node (ref "R1") (pin "1") (pinfunction "1_1") (pintype "input"))
      (node (ref "R13") (pin "1") (pinfunction "1_1") (pintype "input"))
      (node (ref "R17") (pin "1") (pinfunction "1_1") (pintype "input"))
      (node (ref "R18") (pin "1") (pinfunction "1_1") (pintype "input"))
      (node (ref "R19") (pin "2") (pinfunction "2_2") (pintype "input"))
      (node (ref "R4") (pin "2") (pinfunction "2_2") (pintype "input"))
      (node (ref "R7") (pin "2") (pinfunction "2_2") (pintype "input"))
      (node (ref "U1") (pin "1") (pinfunction "VDD_1") (pintype "unspecified"))
      (node (ref "U1") (pin "17") (pinfunction "VDD_17") (pintype "unspecified"))
      (node (ref "U11") (pin "1") (pinfunction "1_1") (pintype "unspecified"))
      (node (ref "U12") (pin "1") (pinfunction "1_1") (pintype "unspecified"))
      (node (ref "U13") (pin "1") (pinfunction "1_1") (pintype "unspecified"))
      (node (ref "U18") (pin "12") (pinfunction "VDD3V_12") (pintype "unspecified"))
      (node (ref "U2") (pin "26") (pinfunction "VREF_26") (pintype "input"))
      (node (ref "U2") (pin "33") (pinfunction "ENABLE_33") (pintype "input"))
      (node (ref "U20") (pin "1") (pinfunction "1_1") (pintype "input"))
      (node (ref "U3") (pin "3") (pinfunction "VCC_3") (pintype "unspecified"))
    )
    (net (code "2") (name "3.3VA") (class "Default")
      (node (ref "U1") (pin "15") (pinfunction "VDDA_15") (pintype "unspecified"))
      (node (ref "U10") (pin "1") (pinfunction "1_1") (pintype "unspecified"))
      (node (ref "U13") (pin "2") (pinfunction "2_2") (pintype "unspecified"))
    )
    (net (code "3") (name "24V") (class "Default")
      (node (ref "C13") (pin "1") (pinfunction "1_1") (pintype "unspecified"))
      (node (ref "C14") (pin "1") (pinfunction "1_1") (pintype "unspecified"))
      (node (ref "C15") (pin "2") (pinfunction "2_2") (pintype "input"))
      (node (ref "C16") (pin "2") (pinfunction "2_2") (pintype "input"))
      (node (ref "C17") (pin "2") (pinfunction "2_2") (pintype "input"))
      (node (ref "C18") (pin "2") (pinfunction "2_2") (pintype "input"))
      (node (ref "C19") (pin "2") (pinfunction "2_2") (pintype "input"))
      (node (ref "C20") (pin "2") (pinfunction "2_2") (pintype "input"))
      (node (ref "C21") (pin "2") (pinfunction "2_2") (pintype "input"))
      (node (ref "C22") (pin "2") (pinfunction "2_2") (pintype "input"))
      (node (ref "C23") (pin "2") (pinfunction "2_2") (pintype "input"))
      (node (ref "C24") (pin "2") (pinfunction "2_2") (pintype "input"))
      (node (ref "C25") (pin "2") (pinfunction "2_2") (pintype "input"))
      (node (ref "C26") (pin "2") (pinfunction "2_2") (pintype "input"))
      (node (ref "C27") (pin "2") (pinfunction "2_2") (pintype "input"))
      (node (ref "C28") (pin "2") (pinfunction "2_2") (pintype "input"))
      (node (ref "C29") (pin "2") (pinfunction "2_2") (pintype "input"))
      (node (ref "C30") (pin "2") (pinfunction "2_2") (pintype "input"))
      (node (ref "C31") (pin "2") (pinfunction "2_2") (pintype "input"))
      (node (ref "C32") (pin "2") (pinfunction "2_2") (pintype "input"))
      (node (ref "C33") (pin "2") (pinfunction "2_2") (pintype "input"))
      (node (ref "C34") (pin "2") (pinfunction "2_2") (pintype "input"))
      (node (ref "C35") (pin "2") (pinfunction "2_2") (pintype "input"))
      (node (ref "C36") (pin "2") (pinfunction "2_2") (pintype "input"))
      (node (ref "C37") (pin "2") (pinfunction "2_2") (pintype "input"))
      (node (ref "C38") (pin "2") (pinfunction "2_2") (pintype "input"))
      (node (ref "C39") (pin "2") (pinfunction "2_2") (pintype "input"))
      (node (ref "C40") (pin "2") (pinfunction "2_2") (pintype "input"))
      (node (ref "C41") (pin "2") (pinfunction "2_2") (pintype "input"))
      (node (ref "C42") (pin "2") (pinfunction "2_2") (pintype "input"))
      (node (ref "C43") (pin "2") (pinfunction "2_2") (pintype "input"))
      (node (ref "C44") (pin "2") (pinfunction "2_2") (pintype "input"))
      (node (ref "C45") (pin "2") (pinfunction "2_2") (pintype "input"))
      (node (ref "C46") (pin "2") (pinfunction "2_2") (pintype "input"))
      (node (ref "C47") (pin "2") (pinfunction "2_2") (pintype "input"))
      (node (ref "C48") (pin "2") (pinfunction "2_2") (pintype "input"))
      (node (ref "C49") (pin "2") (pinfunction "2_2") (pintype "input"))
      (node (ref "C50") (pin "2") (pinfunction "2_2") (pintype "input"))
      (node (ref "C51") (pin "2") (pinfunction "2_2") (pintype "input"))
      (node (ref "C52") (pin "2") (pinfunction "2_2") (pintype "input"))
      (node (ref "C53") (pin "2") (pinfunction "2_2") (pintype "input"))
      (node (ref "C54") (pin "2") (pinfunction "2_2") (pintype "input"))
      (node (ref "C6") (pin "1") (pinfunction "1_1") (pintype "input"))
      (node (ref "C7") (pin "1") (pinfunction "1_1") (pintype "input"))
      (node (ref "C8") (pin "1") (pinfunction "1_1") (pintype "unspecified"))
      (node (ref "U19") (pin "2") (pinfunction "2_2") (pintype "unspecified"))
      (node (ref "U2") (pin "47") (pinfunction "VIN_47") (pintype "input"))
      (node (ref "U2") (pin "6") (pinfunction "VM_6") (pintype "input"))
      (node (ref "U2") (pin "7") (pinfunction "VDRAIN_7") (pintype "input"))
      (node (ref "U4") (pin "5") (pinfunction "D_5") (pintype "input"))
      (node (ref "U4") (pin "6") (pinfunction "D_6") (pintype "input"))
      (node (ref "U4") (pin "7") (pinfunction "D_7") (pintype "input"))
      (node (ref "U4") (pin "8") (pinfunction "D_8") (pintype "input"))
      (node (ref "U6") (pin "5") (pinfunction "D_5") (pintype "input"))
      (node (ref "U6") (pin "6") (pinfunction "D_6") (pintype "input"))
      (node (ref "U6") (pin "7") (pinfunction "D_7") (pintype "input"))
      (node (ref "U6") (pin "8") (pinfunction "D_8") (pintype "input"))
      (node (ref "U8") (pin "5") (pinfunction "D_5") (pintype "input"))
      (node (ref "U8") (pin "6") (pinfunction "D_6") (pintype "input"))
      (node (ref "U8") (pin "7") (pinfunction "D_7") (pintype "input"))
      (node (ref "U8") (pin "8") (pinfunction "D_8") (pintype "input"))
    )
    (net (code "4") (name "BAT-") (class "Default")
      (node (ref "C15") (pin "1") (pinfunction "1_1") (pintype "input"))
      (node (ref "C16") (pin "1") (pinfunction "1_1") (pintype "input"))
      (node (ref "C17") (pin "1") (pinfunction "1_1") (pintype "input"))
      (node (ref "C18") (pin "1") (pinfunction "1_1") (pintype "input"))
      (node (ref "C19") (pin "1") (pinfunction "1_1") (pintype "input"))
      (node (ref "C20") (pin "1") (pinfunction "1_1") (pintype "input"))
      (node (ref "C21") (pin "1") (pinfunction "1_1") (pintype "input"))
      (node (ref "C22") (pin "1") (pinfunction "1_1") (pintype "input"))
      (node (ref "C23") (pin "1") (pinfunction "1_1") (pintype "input"))
      (node (ref "C24") (pin "1") (pinfunction "1_1") (pintype "input"))
      (node (ref "C25") (pin "1") (pinfunction "1_1") (pintype "input"))
      (node (ref "C26") (pin "1") (pinfunction "1_1") (pintype "input"))
      (node (ref "C27") (pin "1") (pinfunction "1_1") (pintype "input"))
      (node (ref "C28") (pin "1") (pinfunction "1_1") (pintype "input"))
      (node (ref "C29") (pin "1") (pinfunction "1_1") (pintype "input"))
      (node (ref "C30") (pin "1") (pinfunction "1_1") (pintype "input"))
      (node (ref "C31") (pin "1") (pinfunction "1_1") (pintype "input"))
      (node (ref "C32") (pin "1") (pinfunction "1_1") (pintype "input"))
      (node (ref "C33") (pin "1") (pinfunction "1_1") (pintype "input"))
      (node (ref "C34") (pin "1") (pinfunction "1_1") (pintype "input"))
      (node (ref "C35") (pin "1") (pinfunction "1_1") (pintype "input"))
      (node (ref "C36") (pin "1") (pinfunction "1_1") (pintype "input"))
      (node (ref "C37") (pin "1") (pinfunction "1_1") (pintype "input"))
      (node (ref "C38") (pin "1") (pinfunction "1_1") (pintype "input"))
      (node (ref "C39") (pin "1") (pinfunction "1_1") (pintype "input"))
      (node (ref "C40") (pin "1") (pinfunction "1_1") (pintype "input"))
      (node (ref "C41") (pin "1") (pinfunction "1_1") (pintype "input"))
      (node (ref "C42") (pin "1") (pinfunction "1_1") (pintype "input"))
      (node (ref "C43") (pin "1") (pinfunction "1_1") (pintype "input"))
      (node (ref "C44") (pin "1") (pinfunction "1_1") (pintype "input"))
      (node (ref "C45") (pin "1") (pinfunction "1_1") (pintype "input"))
      (node (ref "C46") (pin "1") (pinfunction "1_1") (pintype "input"))
      (node (ref "C47") (pin "1") (pinfunction "1_1") (pintype "input"))
      (node (ref "C48") (pin "1") (pinfunction "1_1") (pintype "input"))
      (node (ref "C49") (pin "1") (pinfunction "1_1") (pintype "input"))
      (node (ref "C50") (pin "1") (pinfunction "1_1") (pintype "input"))
      (node (ref "C51") (pin "1") (pinfunction "1_1") (pintype "input"))
      (node (ref "C52") (pin "1") (pinfunction "1_1") (pintype "input"))
      (node (ref "C53") (pin "1") (pinfunction "1_1") (pintype "input"))
      (node (ref "C54") (pin "1") (pinfunction "1_1") (pintype "input"))
      (node (ref "C6") (pin "2") (pinfunction "2_2") (pintype "input"))
      (node (ref "C7") (pin "2") (pinfunction "2_2") (pintype "input"))
      (node (ref "R15") (pin "2") (pinfunction "2_2") (pintype "input"))
      (node (ref "R5") (pin "1") (pinfunction "1_1") (pintype "input"))
      (node (ref "R6") (pin "2") (pinfunction "2_2") (pintype "input"))
      (node (ref "U19") (pin "1") (pinfunction "1_1") (pintype "unspecified"))
      (node (ref "U2") (pin "12") (pinfunction "SNA_12") (pintype "input"))
      (node (ref "U2") (pin "13") (pinfunction "SNB_13") (pintype "input"))
      (node (ref "U2") (pin "2") (pinfunction "PGND_2") (pintype "input"))
      (node (ref "U2") (pin "21") (pinfunction "SPC_21") (pintype "input"))
      (node (ref "U2") (pin "22") (pinfunction "SNC_22") (pintype "input"))
      (node (ref "U9") (pin "1") (pinfunction "S_1") (pintype "input"))
      (node (ref "U9") (pin "2") (pinfunction "S_2") (pintype "input"))
      (node (ref "U9") (pin "3") (pinfunction "S_3") (pintype "input"))
    )
    (net (code "5") (name "CAL") (class "Default")
      (node (ref "U2") (pin "34") (pinfunction "CAL_34") (pintype "input"))
    )
    (net (code "6") (name "CANH") (class "Default")
      (node (ref "CN1") (pin "1") (pinfunction "1_1") (pintype "input"))
      (node (ref "CN1") (pin "4") (pinfunction "4_4") (pintype "input"))
      (node (ref "R16") (pin "2") (pinfunction "2_2") (pintype "input"))
      (node (ref "U3") (pin "7") (pinfunction "CANH_7") (pintype "unspecified"))
    )
    (net (code "7") (name "CANL") (class "Default")
      (node (ref "CN1") (pin "2") (pinfunction "2_2") (pintype "input"))
      (node (ref "CN1") (pin "3") (pinfunction "3_3") (pintype "input"))
      (node (ref "R16") (pin "1") (pinfunction "1_1") (pintype "input"))
      (node (ref "U3") (pin "6") (pinfunction "CANL_6") (pintype "unspecified"))
    )
    (net (code "8") (name "CLK_MAG") (class "Default")
      (node (ref "U1") (pin "10") (pinfunction "PA5_10") (pintype "unspecified"))
      (node (ref "U18") (pin "2") (pinfunction "CLK_2") (pintype "unspecified"))
    )
    (net (code "9") (name "CS_MAG") (class "Default")
      (node (ref "R1") (pin "2") (pinfunction "2_2") (pintype "input"))
      (node (ref "R19") (pin "1") (pinfunction "1_1") (pintype "input"))
      (node (ref "U1") (pin "9") (pinfunction "PA4_9") (pintype "unspecified"))
      (node (ref "U18") (pin "1") (pinfunction "CSn_1") (pintype "unspecified"))
    )
    (net (code "10") (name "DVDD") (class "Default")
      (node (ref "C10") (pin "2") (pinfunction "2_2") (pintype "unspecified"))
      (node (ref "U2") (pin "36") (pinfunction "DVDD_36") (pintype "input"))
    )
    (net (code "11") (name "ENABLE") (class "Default")
      (node (ref "U1") (pin "13") (pinfunction "PB0_13") (pintype "unspecified"))
      (node (ref "U2") (pin "38") (pinfunction "INLA_38") (pintype "input"))
      (node (ref "U2") (pin "40") (pinfunction "INLB_40") (pintype "input"))
      (node (ref "U2") (pin "42") (pinfunction "INLC_42") (pintype "input"))
    )
    (net (code "12") (name "ENC_A") (class "Default")
      (node (ref "H2") (pin "3") (pinfunction "3_3") (pintype "unspecified"))
      (node (ref "R17") (pin "2") (pinfunction "2_2") (pintype "input"))
      (node (ref "U1") (pin "30") (pinfunction "PB7_30") (pintype "unspecified"))
    )
    (net (code "13") (name "ENC_B") (class "Default")
      (node (ref "H2") (pin "2") (pinfunction "2_2") (pintype "unspecified"))
      (node (ref "R18") (pin "2") (pinfunction "2_2") (pintype "input"))
      (node (ref "U1") (pin "29") (pinfunction "PB6_29") (pintype "unspecified"))
    )
    (net (code "14") (name "FB") (class "Default")
      (node (ref "R13") (pin "2") (pinfunction "2_2") (pintype "input"))
      (node (ref "R14") (pin "1") (pinfunction "1_1") (pintype "input"))
      (node (ref "U2") (pin "1") (pinfunction "FB_1") (pintype "input"))
    )
    (net (code "15") (name "FDCAN_RX") (class "Default")
      (node (ref "U1") (pin "21") (pinfunction "PA11_21") (pintype "unspecified"))
      (node (ref "U3") (pin "4") (pinfunction "RXD_4") (pintype "unspecified"))
    )
    (net (code "16") (name "FDCAN_TX") (class "Default")
      (node (ref "U1") (pin "22") (pinfunction "PA12_22") (pintype "unspecified"))
      (node (ref "U3") (pin "1") (pinfunction "TXD_1") (pintype "unspecified"))
    )
    (net (code "17") (name "GHA") (class "Default")
      (node (ref "U2") (pin "8") (pinfunction "GHA_8") (pintype "input"))
      (node (ref "U4") (pin "4") (pinfunction "G_4") (pintype "input"))
    )
    (net (code "18") (name "GHB") (class "Default")
      (node (ref "U2") (pin "17") (pinfunction "GHB_17") (pintype "input"))
      (node (ref "U6") (pin "4") (pinfunction "G_4") (pintype "input"))
    )
    (net (code "19") (name "GHC") (class "Default")
      (node (ref "U2") (pin "18") (pinfunction "GHC_18") (pintype "input"))
      (node (ref "U8") (pin "4") (pinfunction "G_4") (pintype "input"))
    )
    (net (code "20") (name "GLA") (class "Default")
      (node (ref "U2") (pin "10") (pinfunction "GLA_10") (pintype "input"))
      (node (ref "U5") (pin "4") (pinfunction "G_4") (pintype "input"))
    )
    (net (code "21") (name "GLB") (class "Default")
      (node (ref "U2") (pin "15") (pinfunction "GLB_15") (pintype "input"))
      (node (ref "U7") (pin "4") (pinfunction "G_4") (pintype "input"))
    )
    (net (code "22") (name "GLC") (class "Default")
      (node (ref "U2") (pin "20") (pinfunction "GLC_20") (pintype "input"))
      (node (ref "U9") (pin "4") (pinfunction "G_4") (pintype "input"))
    )
    (net (code "23") (name "GND") (class "Default")
      (node (ref "C1") (pin "1") (pinfunction "1_1") (pintype "input"))
      (node (ref "C10") (pin "1") (pinfunction "1_1") (pintype "unspecified"))
      (node (ref "C12") (pin "2") (pinfunction "2_2") (pintype "unspecified"))
      (node (ref "C13") (pin "2") (pinfunction "2_2") (pintype "unspecified"))
      (node (ref "C14") (pin "2") (pinfunction "2_2") (pintype "unspecified"))
      (node (ref "C2") (pin "1") (pinfunction "1_1") (pintype "input"))
      (node (ref "C55") (pin "1") (pinfunction "1_1") (pintype "unspecified"))
      (node (ref "C56") (pin "1") (pinfunction "1_1") (pintype "input"))
      (node (ref "C57") (pin "2") (pinfunction "2_2") (pintype "input"))
      (node (ref "C58") (pin "1") (pinfunction "1_1") (pintype "input"))
      (node (ref "C59") (pin "1") (pinfunction "1_1") (pintype "unspecified"))
      (node (ref "C9") (pin "1") (pinfunction "1_1") (pintype "input"))
      (node (ref "D1") (pin "2") (pinfunction "A_2") (pintype "input"))
      (node (ref "H2") (pin "1") (pinfunction "1_1") (pintype "unspecified"))
      (node (ref "LED1") (pin "1") (pinfunction "-_1") (pintype "input"))
      (node (ref "R10") (pin "2") (pinfunction "2_2") (pintype "input"))
      (node (ref "R11") (pin "2") (pinfunction "2_2") (pintype "input"))
      (node (ref "R12") (pin "2") (pinfunction "2_2") (pintype "input"))
      (node (ref "R14") (pin "2") (pinfunction "2_2") (pintype "input"))
      (node (ref "R15") (pin "1") (pinfunction "1_1") (pintype "input"))
      (node (ref "R9") (pin "2") (pinfunction "2_2") (pintype "input"))
      (node (ref "U1") (pin "14") (pinfunction "VSSA_14") (pintype "unspecified"))
      (node (ref "U1") (pin "16") (pinfunction "VSS_16") (pintype "unspecified"))
      (node (ref "U1") (pin "31") (pinfunction "PB8-BOOT0_31") (pintype "unspecified"))
      (node (ref "U1") (pin "32") (pinfunction "VSS_32") (pintype "unspecified"))
      (node (ref "U10") (pin "2") (pinfunction "2_2") (pintype "unspecified"))
      (node (ref "U11") (pin "2") (pinfunction "2_2") (pintype "unspecified"))
      (node (ref "U12") (pin "2") (pinfunction "2_2") (pintype "unspecified"))
      (node (ref "U18") (pin "13") (pinfunction "GND_13") (pintype "unspecified"))
      (node (ref "U2") (pin "27") (pinfunction "DGND_27") (pintype "input"))
      (node (ref "U2") (pin "35") (pinfunction "AGND_35") (pintype "input"))
      (node (ref "U2") (pin "43") (pinfunction "BGND_43") (pintype "input"))
      (node (ref "U20") (pin "2") (pinfunction "2_2") (pintype "input"))
      (node (ref "U3") (pin "2") (pinfunction "GND_2") (pintype "unspecified"))
    )
    (net (code "24") (name "LP_SOA") (class "Default")
      (node (ref "C57") (pin "1") (pinfunction "1_1") (pintype "input"))
      (node (ref "U1") (pin "5") (pinfunction "PA0_5") (pintype "unspecified"))
      (node (ref "U14") (pin "2") (pinfunction "2_2") (pintype "unspecified"))
    )
    (net (code "25") (name "LP_SOB") (class "Default")
      (node (ref "C58") (pin "2") (pinfunction "2_2") (pintype "input"))
      (node (ref "U1") (pin "6") (pinfunction "PA1_6") (pintype "unspecified"))
      (node (ref "U15") (pin "2") (pinfunction "2_2") (pintype "unspecified"))
    )
    (net (code "26") (name "MISO_MAG") (class "Default")
      (node (ref "U1") (pin "11") (pinfunction "PA6_11") (pintype "unspecified"))
      (node (ref "U18") (pin "3") (pinfunction "MISO_3") (pintype "unspecified"))
    )
    (net (code "27") (name "MOSI_MAG") (class "Default")
      (node (ref "U1") (pin "12") (pinfunction "PA7_12") (pintype "unspecified"))
      (node (ref "U18") (pin "4") (pinfunction "MOSI_4") (pintype "unspecified"))
    )
    (net (code "28") (name "NFAULT") (class "Default")
      (node (ref "R7") (pin "1") (pinfunction "1_1") (pintype "input"))
      (node (ref "R8") (pin "1") (pinfunction "1_1") (pintype "input"))
      (node (ref "U2") (pin "28") (pinfunction "nFAULT_28") (pintype "input"))
    )
    (net (code "29") (name "Net-(D1-C)") (class "Default")
      (node (ref "C11") (pin "1") (pinfunction "1_1") (pintype "input"))
      (node (ref "D1") (pin "1") (pinfunction "C_1") (pintype "input"))
      (node (ref "L2") (pin "1") (pinfunction "1_1") (pintype "input"))
      (node (ref "U2") (pin "45") (pinfunction "SW_45") (pintype "input"))
    )
    (net (code "30") (name "Net-(LED1-+)") (class "Default")
      (node (ref "LED1") (pin "2") (pinfunction "+_2") (pintype "input"))
      (node (ref "R4") (pin "1") (pinfunction "1_1") (pintype "input"))
    )
    (net (code "31") (name "Net-(LED2--)") (class "Default")
      (node (ref "LED2") (pin "1") (pinfunction "-_1") (pintype "input"))
      (node (ref "R8") (pin "2") (pinfunction "2_2") (pintype "input"))
    )
    (net (code "32") (name "Net-(U2-CB)") (class "Default")
      (node (ref "C11") (pin "2") (pinfunction "2_2") (pintype "input"))
      (node (ref "U2") (pin "44") (pinfunction "CB_44") (pintype "input"))
    )
    (net (code "33") (name "Net-(U2-CPH)") (class "Default")
      (node (ref "C5") (pin "1") (pinfunction "1_1") (pintype "input"))
      (node (ref "U2") (pin "4") (pinfunction "CPH_4") (pintype "input"))
    )
    (net (code "34") (name "Net-(U2-CPL)") (class "Default")
      (node (ref "C5") (pin "2") (pinfunction "2_2") (pintype "input"))
      (node (ref "U2") (pin "3") (pinfunction "CPL_3") (pintype "input"))
    )
    (net (code "35") (name "Net-(U2-GAIN)") (class "Default")
      (node (ref "R10") (pin "1") (pinfunction "1_1") (pintype "input"))
      (node (ref "U2") (pin "32") (pinfunction "GAIN_32") (pintype "input"))
    )
    (net (code "36") (name "Net-(U2-IDRIVE)") (class "Default")
      (node (ref "R12") (pin "1") (pinfunction "1_1") (pintype "input"))
      (node (ref "U2") (pin "30") (pinfunction "IDRIVE_30") (pintype "input"))
    )
    (net (code "37") (name "Net-(U2-MODE)") (class "Default")
      (node (ref "R9") (pin "1") (pinfunction "1_1") (pintype "input"))
      (node (ref "U2") (pin "29") (pinfunction "MODE_29") (pintype "input"))
    )
    (net (code "38") (name "Net-(U2-VCP)") (class "Default")
      (node (ref "C8") (pin "2") (pinfunction "2_2") (pintype "unspecified"))
      (node (ref "U2") (pin "5") (pinfunction "VCP_5") (pintype "input"))
    )
    (net (code "39") (name "Net-(U2-VDS)") (class "Default")
      (node (ref "R11") (pin "1") (pinfunction "1_1") (pintype "input"))
      (node (ref "U2") (pin "31") (pinfunction "VDS_31") (pintype "input"))
    )
    (net (code "40") (name "PHASEA") (class "Default")
      (node (ref "U2") (pin "9") (pinfunction "SHA_9") (pintype "input"))
      (node (ref "U4") (pin "1") (pinfunction "S_1") (pintype "input"))
      (node (ref "U4") (pin "2") (pinfunction "S_2") (pintype "input"))
      (node (ref "U4") (pin "3") (pinfunction "S_3") (pintype "input"))
      (node (ref "U5") (pin "5") (pinfunction "D_5") (pintype "input"))
      (node (ref "U5") (pin "6") (pinfunction "D_6") (pintype "input"))
      (node (ref "U5") (pin "7") (pinfunction "D_7") (pintype "input"))
      (node (ref "U5") (pin "8") (pinfunction "D_8") (pintype "input"))
    )
    (net (code "41") (name "PHASEB") (class "Default")
      (node (ref "U2") (pin "16") (pinfunction "SHB_16") (pintype "input"))
      (node (ref "U6") (pin "1") (pinfunction "S_1") (pintype "input"))
      (node (ref "U6") (pin "2") (pinfunction "S_2") (pintype "input"))
      (node (ref "U6") (pin "3") (pinfunction "S_3") (pintype "input"))
      (node (ref "U7") (pin "5") (pinfunction "D_5") (pintype "input"))
      (node (ref "U7") (pin "6") (pinfunction "D_6") (pintype "input"))
      (node (ref "U7") (pin "7") (pinfunction "D_7") (pintype "input"))
      (node (ref "U7") (pin "8") (pinfunction "D_8") (pintype "input"))
    )
    (net (code "42") (name "PHASEC") (class "Default")
      (node (ref "U2") (pin "19") (pinfunction "SHC_19") (pintype "input"))
      (node (ref "U8") (pin "1") (pinfunction "S_1") (pintype "input"))
      (node (ref "U8") (pin "2") (pinfunction "S_2") (pintype "input"))
      (node (ref "U8") (pin "3") (pinfunction "S_3") (pintype "input"))
      (node (ref "U9") (pin "5") (pinfunction "D_5") (pintype "input"))
      (node (ref "U9") (pin "6") (pinfunction "D_6") (pintype "input"))
      (node (ref "U9") (pin "7") (pinfunction "D_7") (pintype "input"))
      (node (ref "U9") (pin "8") (pinfunction "D_8") (pintype "input"))
    )
    (net (code "43") (name "PWMA") (class "Default")
      (node (ref "U1") (pin "20") (pinfunction "PA10_20") (pintype "unspecified"))
      (node (ref "U2") (pin "37") (pinfunction "INHA_37") (pintype "input"))
    )
    (net (code "44") (name "PWMB") (class "Default")
      (node (ref "U1") (pin "19") (pinfunction "PA9_19") (pintype "unspecified"))
      (node (ref "U2") (pin "39") (pinfunction "INHB_39") (pintype "input"))
    )
    (net (code "45") (name "PWMC") (class "Default")
      (node (ref "U1") (pin "18") (pinfunction "PA8_18") (pintype "unspecified"))
      (node (ref "U2") (pin "41") (pinfunction "INHC_41") (pintype "input"))
    )
    (net (code "46") (name "SOA") (class "Default")
      (node (ref "U14") (pin "1") (pinfunction "1_1") (pintype "unspecified"))
      (node (ref "U2") (pin "25") (pinfunction "SOA_25") (pintype "input"))
    )
    (net (code "47") (name "SOB") (class "Default")
      (node (ref "U15") (pin "1") (pinfunction "1_1") (pintype "unspecified"))
      (node (ref "U2") (pin "24") (pinfunction "SOB_24") (pintype "input"))
    )
    (net (code "48") (name "SOC") (class "Default")
      (node (ref "U2") (pin "23") (pinfunction "SOC_23") (pintype "input"))
    )
    (net (code "49") (name "SPA") (class "Default")
      (node (ref "R5") (pin "2") (pinfunction "2_2") (pintype "input"))
      (node (ref "U2") (pin "11") (pinfunction "SPA_11") (pintype "input"))
      (node (ref "U5") (pin "1") (pinfunction "S_1") (pintype "input"))
      (node (ref "U5") (pin "2") (pinfunction "S_2") (pintype "input"))
      (node (ref "U5") (pin "3") (pinfunction "S_3") (pintype "input"))
    )
    (net (code "50") (name "SPB") (class "Default")
      (node (ref "R6") (pin "1") (pinfunction "1_1") (pintype "input"))
      (node (ref "U2") (pin "14") (pinfunction "SPB_14") (pintype "input"))
      (node (ref "U7") (pin "1") (pinfunction "S_1") (pintype "input"))
      (node (ref "U7") (pin "2") (pinfunction "S_2") (pintype "input"))
      (node (ref "U7") (pin "3") (pinfunction "S_3") (pintype "input"))
    )
    (net (code "51") (name "SWCLK") (class "Default")
      (node (ref "U1") (pin "24") (pinfunction "PA14_24") (pintype "unspecified"))
      (node (ref "U20") (pin "4") (pinfunction "4_4") (pintype "input"))
    )
    (net (code "52") (name "SWIO") (class "Default")
      (node (ref "U1") (pin "23") (pinfunction "PA13_23") (pintype "unspecified"))
      (node (ref "U20") (pin "3") (pinfunction "3_3") (pintype "input"))
    )
    (net (code "53") (name "SWO") (class "Default")
      (node (ref "U1") (pin "26") (pinfunction "PB3_26") (pintype "unspecified"))
    )
    (net (code "54") (name "unconnected-(CN1-Pad5)") (class "Default")
      (node (ref "CN1") (pin "5") (pinfunction "5_5") (pintype "input"))
    )
    (net (code "55") (name "unconnected-(CN1-Pad6)") (class "Default")
      (node (ref "CN1") (pin "6") (pinfunction "6_6") (pintype "input"))
    )
    (net (code "56") (name "unconnected-(U1-PA2-Pad7)") (class "Default")
      (node (ref "U1") (pin "7") (pinfunction "PA2_7") (pintype "unspecified"))
    )
    (net (code "57") (name "unconnected-(U1-PA3-Pad8)") (class "Default")
      (node (ref "U1") (pin "8") (pinfunction "PA3_8") (pintype "unspecified"))
    )
    (net (code "58") (name "unconnected-(U1-PA15-Pad25)") (class "Default")
      (node (ref "U1") (pin "25") (pinfunction "PA15_25") (pintype "unspecified"))
    )
    (net (code "59") (name "unconnected-(U1-PB4-Pad27)") (class "Default")
      (node (ref "U1") (pin "27") (pinfunction "PB4_27") (pintype "unspecified"))
    )
    (net (code "60") (name "unconnected-(U1-PB5-Pad28)") (class "Default")
      (node (ref "U1") (pin "28") (pinfunction "PB5_28") (pintype "unspecified"))
    )
    (net (code "61") (name "unconnected-(U1-PF0-OSC_IN-Pad2)") (class "Default")
      (node (ref "U1") (pin "2") (pinfunction "PF0-OSC_IN_2") (pintype "unspecified"))
    )
    (net (code "62") (name "unconnected-(U1-PF1-OSC_OUT-Pad3)") (class "Default")
      (node (ref "U1") (pin "3") (pinfunction "PF1-OSC_OUT_3") (pintype "unspecified"))
    )
    (net (code "63") (name "unconnected-(U1-PG10-NRST-Pad4)") (class "Default")
      (node (ref "U1") (pin "4") (pinfunction "PG10-NRST_4") (pintype "unspecified"))
    )
    (net (code "64") (name "unconnected-(U2-EP-Pad49)") (class "Default")
      (node (ref "U2") (pin "49") (pinfunction "EP_49") (pintype "input"))
    )
    (net (code "65") (name "unconnected-(U2-NC-Pad46)") (class "Default")
      (node (ref "U2") (pin "46") (pinfunction "NC_46") (pintype "input"))
    )
    (net (code "66") (name "unconnected-(U2-nSHDN-Pad48)") (class "Default")
      (node (ref "U2") (pin "48") (pinfunction "nSHDN_48") (pintype "input"))
    )
    (net (code "67") (name "unconnected-(U3-NC-Pad5)") (class "Default")
      (node (ref "U3") (pin "5") (pinfunction "NC_5") (pintype "unspecified"))
    )
    (net (code "68") (name "unconnected-(U3-NC-Pad8)") (class "Default")
      (node (ref "U3") (pin "8") (pinfunction "NC_8") (pintype "unspecified"))
    )
    (net (code "69") (name "unconnected-(U18-PWM-Pad14)") (class "Default")
      (node (ref "U18") (pin "14") (pinfunction "PWM_14") (pintype "unspecified"))
    )
    (net (code "70") (name "unconnected-(U18-TEST-Pad5)") (class "Default")
      (node (ref "U18") (pin "5") (pinfunction "TEST_5") (pintype "unspecified"))
    )
    (net (code "71") (name "unconnected-(U18-TEST-Pad6)") (class "Default")
      (node (ref "U18") (pin "6") (pinfunction "TEST_6") (pintype "unspecified"))
    )
    (net (code "72") (name "unconnected-(U18-TEST-Pad7)") (class "Default")
      (node (ref "U18") (pin "7") (pinfunction "TEST_7") (pintype "unspecified"))
    )
    (net (code "73") (name "unconnected-(U18-TEST-Pad8)") (class "Default")
      (node (ref "U18") (pin "8") (pinfunction "TEST_8") (pintype "unspecified"))
    )
    (net (code "74") (name "unconnected-(U18-TEST-Pad9)") (class "Default")
      (node (ref "U18") (pin "9") (pinfunction "TEST_9") (pintype "unspecified"))
    )
    (net (code "75") (name "unconnected-(U18-TEST-Pad10)") (class "Default")
      (node (ref "U18") (pin "10") (pinfunction "TEST_10") (pintype "unspecified"))
    )
    (net (code "76") (name "unconnected-(U18-VDD5V-Pad11)") (class "Default")
      (node (ref "U18") (pin "11") (pinfunction "VDD5V_11") (pintype "unspecified"))
    )
    (net (code "77") (name "unconnected-(U19-Pad3)") (class "Default")
      (node (ref "U19") (pin "3") (pinfunction "3_3") (pintype "unspecified"))
    )
    (net (code "78") (name "unconnected-(U19-Pad4)") (class "Default")
      (node (ref "U19") (pin "4") (pinfunction "4_4") (pintype "unspecified"))
    )
  )
)
